# 15-I225-MISC.net
KiCad netlist of a schematic drawn in Altium Designer
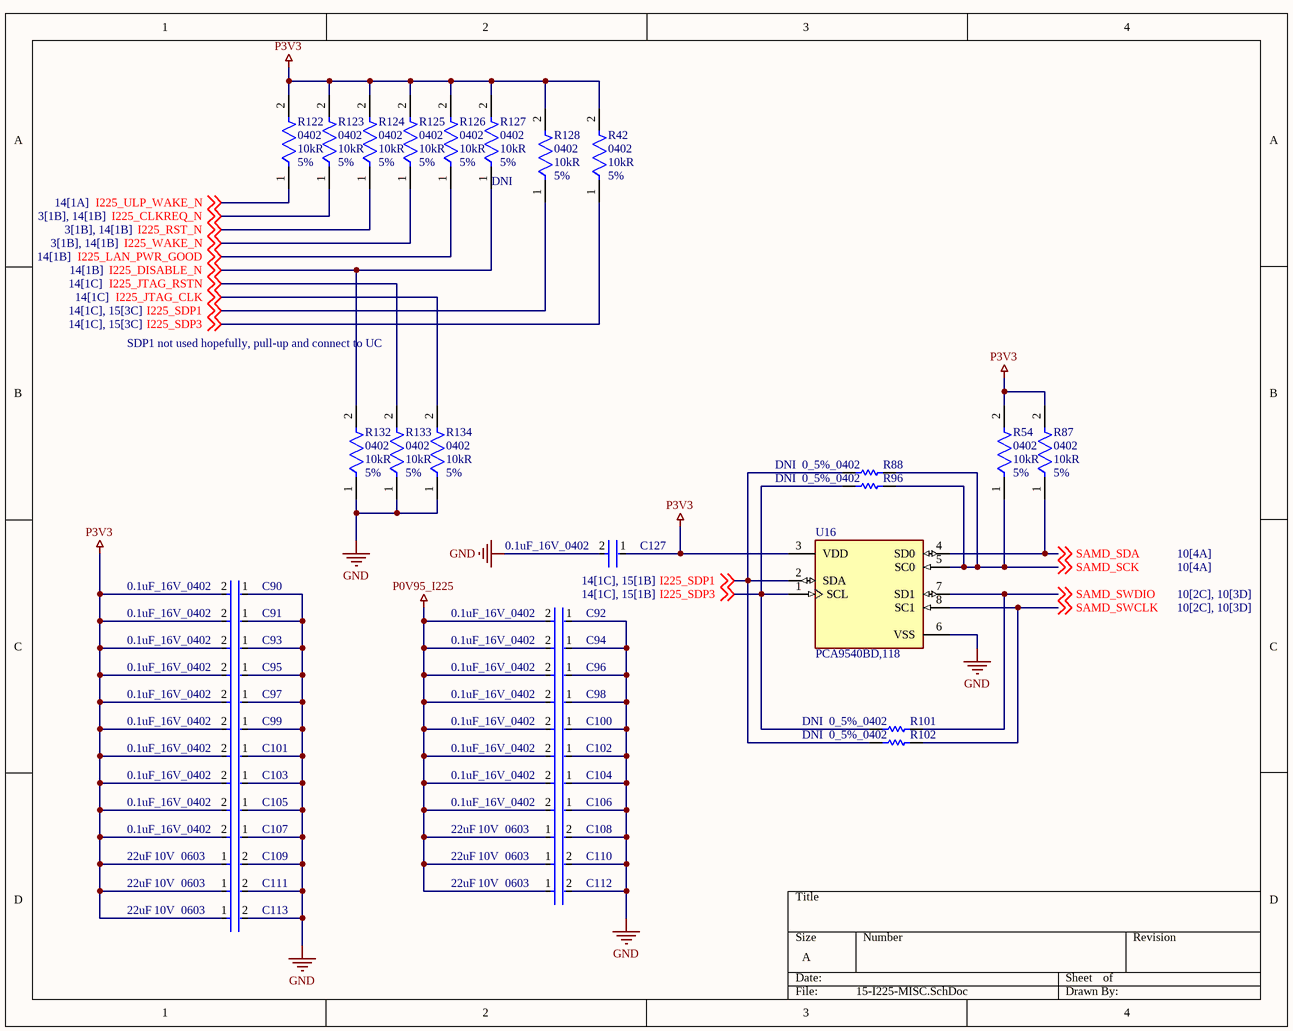
[diagram p0: 15-I225-MISC.SchDoc]

(export (version "E")
  (design (tool "Eeschema 10.0.6"))
  (components
    (comp (ref "C90")
      (value "0.1uF_16V_0402")
      (footprint "FP-GRM15-MFG")
      (description "CAP CER 0.1UF 16V X7R 0402")
      (fields (field (name "MANUFACTURER PART NUMBER") "GRM155R71C104KA88D") (field (name "TOLERANCE") "10%"))
      (libsource (lib "Altium Content Vault") (part "236180d848d6139a670b325ea6854c9"))
    )
    (comp (ref "C91")
      (value "0.1uF_16V_0402")
      (footprint "FP-GRM15-MFG")
      (description "CAP CER 0.1UF 16V X7R 0402")
      (fields (field (name "MANUFACTURER PART NUMBER") "GRM155R71C104KA88D") (field (name "TOLERANCE") "10%"))
      (libsource (lib "Altium Content Vault") (part "236180d848d6139a670b325ea6854c9"))
    )
    (comp (ref "C92")
      (value "0.1uF_16V_0402")
      (footprint "FP-GRM15-MFG")
      (description "CAP CER 0.1UF 16V X7R 0402")
      (fields (field (name "MANUFACTURER PART NUMBER") "GRM155R71C104KA88D") (field (name "TOLERANCE") "10%"))
      (libsource (lib "Altium Content Vault") (part "236180d848d6139a670b325ea6854c9"))
    )
    (comp (ref "C93")
      (value "0.1uF_16V_0402")
      (footprint "FP-GRM15-MFG")
      (description "CAP CER 0.1UF 16V X7R 0402")
      (fields (field (name "MANUFACTURER PART NUMBER") "GRM155R71C104KA88D") (field (name "TOLERANCE") "10%"))
      (libsource (lib "Altium Content Vault") (part "236180d848d6139a670b325ea6854c9"))
    )
    (comp (ref "C94")
      (value "0.1uF_16V_0402")
      (footprint "FP-GRM15-MFG")
      (description "CAP CER 0.1UF 16V X7R 0402")
      (fields (field (name "MANUFACTURER PART NUMBER") "GRM155R71C104KA88D") (field (name "TOLERANCE") "10%"))
      (libsource (lib "Altium Content Vault") (part "236180d848d6139a670b325ea6854c9"))
    )
    (comp (ref "C95")
      (value "0.1uF_16V_0402")
      (footprint "FP-GRM15-MFG")
      (description "CAP CER 0.1UF 16V X7R 0402")
      (fields (field (name "MANUFACTURER PART NUMBER") "GRM155R71C104KA88D") (field (name "TOLERANCE") "10%"))
      (libsource (lib "Altium Content Vault") (part "236180d848d6139a670b325ea6854c9"))
    )
    (comp (ref "C96")
      (value "0.1uF_16V_0402")
      (footprint "FP-GRM15-MFG")
      (description "CAP CER 0.1UF 16V X7R 0402")
      (fields (field (name "MANUFACTURER PART NUMBER") "GRM155R71C104KA88D") (field (name "TOLERANCE") "10%"))
      (libsource (lib "Altium Content Vault") (part "236180d848d6139a670b325ea6854c9"))
    )
    (comp (ref "C97")
      (value "0.1uF_16V_0402")
      (footprint "FP-GRM15-MFG")
      (description "CAP CER 0.1UF 16V X7R 0402")
      (fields (field (name "MANUFACTURER PART NUMBER") "GRM155R71C104KA88D") (field (name "TOLERANCE") "10%"))
      (libsource (lib "Altium Content Vault") (part "236180d848d6139a670b325ea6854c9"))
    )
    (comp (ref "C98")
      (value "0.1uF_16V_0402")
      (footprint "FP-GRM15-MFG")
      (description "CAP CER 0.1UF 16V X7R 0402")
      (fields (field (name "MANUFACTURER PART NUMBER") "GRM155R71C104KA88D") (field (name "TOLERANCE") "10%"))
      (libsource (lib "Altium Content Vault") (part "236180d848d6139a670b325ea6854c9"))
    )
    (comp (ref "C99")
      (value "0.1uF_16V_0402")
      (footprint "FP-GRM15-MFG")
      (description "CAP CER 0.1UF 16V X7R 0402")
      (fields (field (name "MANUFACTURER PART NUMBER") "GRM155R71C104KA88D") (field (name "TOLERANCE") "10%"))
      (libsource (lib "Altium Content Vault") (part "236180d848d6139a670b325ea6854c9"))
    )
    (comp (ref "C100")
      (value "0.1uF_16V_0402")
      (footprint "FP-GRM15-MFG")
      (description "CAP CER 0.1UF 16V X7R 0402")
      (fields (field (name "MANUFACTURER PART NUMBER") "GRM155R71C104KA88D") (field (name "TOLERANCE") "10%"))
      (libsource (lib "Altium Content Vault") (part "236180d848d6139a670b325ea6854c9"))
    )
    (comp (ref "C101")
      (value "0.1uF_16V_0402")
      (footprint "FP-GRM15-MFG")
      (description "CAP CER 0.1UF 16V X7R 0402")
      (fields (field (name "MANUFACTURER PART NUMBER") "GRM155R71C104KA88D") (field (name "TOLERANCE") "10%"))
      (libsource (lib "Altium Content Vault") (part "236180d848d6139a670b325ea6854c9"))
    )
    (comp (ref "C102")
      (value "0.1uF_16V_0402")
      (footprint "FP-GRM15-MFG")
      (description "CAP CER 0.1UF 16V X7R 0402")
      (fields (field (name "MANUFACTURER PART NUMBER") "GRM155R71C104KA88D") (field (name "TOLERANCE") "10%"))
      (libsource (lib "Altium Content Vault") (part "236180d848d6139a670b325ea6854c9"))
    )
    (comp (ref "C103")
      (value "0.1uF_16V_0402")
      (footprint "FP-GRM15-MFG")
      (description "CAP CER 0.1UF 16V X7R 0402")
      (fields (field (name "MANUFACTURER PART NUMBER") "GRM155R71C104KA88D") (field (name "TOLERANCE") "10%"))
      (libsource (lib "Altium Content Vault") (part "236180d848d6139a670b325ea6854c9"))
    )
    (comp (ref "C104")
      (value "0.1uF_16V_0402")
      (footprint "FP-GRM15-MFG")
      (description "CAP CER 0.1UF 16V X7R 0402")
      (fields (field (name "MANUFACTURER PART NUMBER") "GRM155R71C104KA88D") (field (name "TOLERANCE") "10%"))
      (libsource (lib "Altium Content Vault") (part "236180d848d6139a670b325ea6854c9"))
    )
    (comp (ref "C105")
      (value "0.1uF_16V_0402")
      (footprint "FP-GRM15-MFG")
      (description "CAP CER 0.1UF 16V X7R 0402")
      (fields (field (name "MANUFACTURER PART NUMBER") "GRM155R71C104KA88D") (field (name "TOLERANCE") "10%"))
      (libsource (lib "Altium Content Vault") (part "236180d848d6139a670b325ea6854c9"))
    )
    (comp (ref "C106")
      (value "0.1uF_16V_0402")
      (footprint "FP-GRM15-MFG")
      (description "CAP CER 0.1UF 16V X7R 0402")
      (fields (field (name "MANUFACTURER PART NUMBER") "GRM155R71C104KA88D") (field (name "TOLERANCE") "10%"))
      (libsource (lib "Altium Content Vault") (part "236180d848d6139a670b325ea6854c9"))
    )
    (comp (ref "C107")
      (value "0.1uF_16V_0402")
      (footprint "FP-GRM15-MFG")
      (description "CAP CER 0.1UF 16V X7R 0402")
      (fields (field (name "MANUFACTURER PART NUMBER") "GRM155R71C104KA88D") (field (name "TOLERANCE") "10%"))
      (libsource (lib "Altium Content Vault") (part "236180d848d6139a670b325ea6854c9"))
    )
    (comp (ref "C108")
      (value "GRM188R61A226ME15D")
      (footprint "FP-GRM188-0_2-IPC_C")
      (description "Chip Multilayer Ceramic Capacitors for General Purpose, 0603, 22uF, X5R, 15%, 20%, 10V")
      (fields
        (field (name "TOLERANCE") "20%")
        (field (name "CAPACITANCE") "22uF")
        (field (name "VOLTAGE RATING") "10V")
        (field (name "CASE CODE (IMPERIAL)") "0603")
      )
      (libsource (lib "Altium Content Vault") (part "11868f565c42a9108669ba33697ecf6"))
    )
    (comp (ref "C109")
      (value "GRM188R61A226ME15D")
      (footprint "FP-GRM188-0_2-IPC_C")
      (description "Chip Multilayer Ceramic Capacitors for General Purpose, 0603, 22uF, X5R, 15%, 20%, 10V")
      (fields
        (field (name "TOLERANCE") "20%")
        (field (name "CAPACITANCE") "22uF")
        (field (name "VOLTAGE RATING") "10V")
        (field (name "CASE CODE (IMPERIAL)") "0603")
      )
      (libsource (lib "Altium Content Vault") (part "11868f565c42a9108669ba33697ecf6"))
    )
    (comp (ref "C110")
      (value "GRM188R61A226ME15D")
      (footprint "FP-GRM188-0_2-IPC_C")
      (description "Chip Multilayer Ceramic Capacitors for General Purpose, 0603, 22uF, X5R, 15%, 20%, 10V")
      (fields
        (field (name "TOLERANCE") "20%")
        (field (name "CAPACITANCE") "22uF")
        (field (name "VOLTAGE RATING") "10V")
        (field (name "CASE CODE (IMPERIAL)") "0603")
      )
      (libsource (lib "Altium Content Vault") (part "11868f565c42a9108669ba33697ecf6"))
    )
    (comp (ref "C111")
      (value "GRM188R61A226ME15D")
      (footprint "FP-GRM188-0_2-IPC_C")
      (description "Chip Multilayer Ceramic Capacitors for General Purpose, 0603, 22uF, X5R, 15%, 20%, 10V")
      (fields
        (field (name "TOLERANCE") "20%")
        (field (name "CAPACITANCE") "22uF")
        (field (name "VOLTAGE RATING") "10V")
        (field (name "CASE CODE (IMPERIAL)") "0603")
      )
      (libsource (lib "Altium Content Vault") (part "11868f565c42a9108669ba33697ecf6"))
    )
    (comp (ref "C112")
      (value "GRM188R61A226ME15D")
      (footprint "FP-GRM188-0_2-IPC_C")
      (description "Chip Multilayer Ceramic Capacitors for General Purpose, 0603, 22uF, X5R, 15%, 20%, 10V")
      (fields
        (field (name "TOLERANCE") "20%")
        (field (name "CAPACITANCE") "22uF")
        (field (name "VOLTAGE RATING") "10V")
        (field (name "CASE CODE (IMPERIAL)") "0603")
      )
      (libsource (lib "Altium Content Vault") (part "11868f565c42a9108669ba33697ecf6"))
    )
    (comp (ref "C113")
      (value "GRM188R61A226ME15D")
      (footprint "FP-GRM188-0_2-IPC_C")
      (description "Chip Multilayer Ceramic Capacitors for General Purpose, 0603, 22uF, X5R, 15%, 20%, 10V")
      (fields
        (field (name "TOLERANCE") "20%")
        (field (name "CAPACITANCE") "22uF")
        (field (name "VOLTAGE RATING") "10V")
        (field (name "CASE CODE (IMPERIAL)") "0603")
      )
      (libsource (lib "Altium Content Vault") (part "11868f565c42a9108669ba33697ecf6"))
    )
    (comp (ref "C127")
      (value "0.1uF_16V_0402")
      (footprint "FP-GRM15-MFG")
      (description "CAP CER 0.1UF 16V X7R 0402")
      (fields (field (name "MANUFACTURER PART NUMBER") "GRM155R71C104KA88D") (field (name "TOLERANCE") "10%"))
      (libsource (lib "Altium Content Vault") (part "236180d848d6139a670b325ea6854c9"))
    )
    (comp (ref "R42")
      (value "CRCW040210K0JNED")
      (footprint "FP-CRCW0402-e3-IPC_B")
      (description "RES Thick Film, 10kΩ, 5%, 0.063W, 200ppm/°C, 0402")
      (fields
        (field (name "CASE/PACKAGE") "0402")
        (field (name "RESISTANCE") "10kR")
        (field (name "TOLERANCE") "5%")
      )
      (libsource (lib "Altium Content Vault") (part "1029c3af85768c4190bb7ad29bc67b5"))
    )
    (comp (ref "R54")
      (value "CRCW040210K0JNED")
      (footprint "FP-CRCW0402-e3-IPC_B")
      (description "RES Thick Film, 10kΩ, 5%, 0.063W, 200ppm/°C, 0402")
      (fields
        (field (name "CASE/PACKAGE") "0402")
        (field (name "RESISTANCE") "10kR")
        (field (name "TOLERANCE") "5%")
      )
      (libsource (lib "Altium Content Vault") (part "1029c3af85768c4190bb7ad29bc67b5"))
    )
    (comp (ref "R87")
      (value "CRCW040210K0JNED")
      (footprint "FP-CRCW0402-e3-IPC_B")
      (description "RES Thick Film, 10kΩ, 5%, 0.063W, 200ppm/°C, 0402")
      (fields
        (field (name "CASE/PACKAGE") "0402")
        (field (name "RESISTANCE") "10kR")
        (field (name "TOLERANCE") "5%")
      )
      (libsource (lib "Altium Content Vault") (part "1029c3af85768c4190bb7ad29bc67b5"))
    )
    (comp (ref "R88")
      (value "0_5%_0402")
      (footprint "RESC1005X40X25LL10T10")
      (fields
        (field (name "MANUFACTURER") "KOA Speer")
        (field (name "PART NUMBER") "RK73Z1ETTP")
        (field (name "DNI") "DNI")
      )
      (libsource (lib "Altium Content Vault") (part "RES"))
    )
    (comp (ref "R96")
      (value "0_5%_0402")
      (footprint "RESC1005X40X25LL10T10")
      (fields
        (field (name "MANUFACTURER") "KOA Speer")
        (field (name "PART NUMBER") "RK73Z1ETTP")
        (field (name "DNI") "DNI")
      )
      (libsource (lib "Altium Content Vault") (part "RES"))
    )
    (comp (ref "R101")
      (value "0_5%_0402")
      (footprint "RESC1005X40X25LL10T10")
      (fields
        (field (name "MANUFACTURER") "KOA Speer")
        (field (name "PART NUMBER") "RK73Z1ETTP")
        (field (name "DNI") "DNI")
      )
      (libsource (lib "Altium Content Vault") (part "RES"))
    )
    (comp (ref "R102")
      (value "0_5%_0402")
      (footprint "RESC1005X40X25LL10T10")
      (fields
        (field (name "MANUFACTURER") "KOA Speer")
        (field (name "PART NUMBER") "RK73Z1ETTP")
        (field (name "DNI") "DNI")
      )
      (libsource (lib "Altium Content Vault") (part "RES"))
    )
    (comp (ref "R122")
      (value "CRCW040210K0JNED")
      (footprint "FP-CRCW0402-e3-IPC_B")
      (description "RES Thick Film, 10kΩ, 5%, 0.063W, 200ppm/°C, 0402")
      (fields
        (field (name "CASE/PACKAGE") "0402")
        (field (name "RESISTANCE") "10kR")
        (field (name "TOLERANCE") "5%")
      )
      (libsource (lib "Altium Content Vault") (part "1029c3af85768c4190bb7ad29bc67b5"))
    )
    (comp (ref "R123")
      (value "CRCW040210K0JNED")
      (footprint "FP-CRCW0402-e3-IPC_B")
      (description "RES Thick Film, 10kΩ, 5%, 0.063W, 200ppm/°C, 0402")
      (fields
        (field (name "CASE/PACKAGE") "0402")
        (field (name "RESISTANCE") "10kR")
        (field (name "TOLERANCE") "5%")
      )
      (libsource (lib "Altium Content Vault") (part "1029c3af85768c4190bb7ad29bc67b5"))
    )
    (comp (ref "R124")
      (value "CRCW040210K0JNED")
      (footprint "FP-CRCW0402-e3-IPC_B")
      (description "RES Thick Film, 10kΩ, 5%, 0.063W, 200ppm/°C, 0402")
      (fields
        (field (name "CASE/PACKAGE") "0402")
        (field (name "RESISTANCE") "10kR")
        (field (name "TOLERANCE") "5%")
      )
      (libsource (lib "Altium Content Vault") (part "1029c3af85768c4190bb7ad29bc67b5"))
    )
    (comp (ref "R125")
      (value "CRCW040210K0JNED")
      (footprint "FP-CRCW0402-e3-IPC_B")
      (description "RES Thick Film, 10kΩ, 5%, 0.063W, 200ppm/°C, 0402")
      (fields
        (field (name "CASE/PACKAGE") "0402")
        (field (name "RESISTANCE") "10kR")
        (field (name "TOLERANCE") "5%")
      )
      (libsource (lib "Altium Content Vault") (part "1029c3af85768c4190bb7ad29bc67b5"))
    )
    (comp (ref "R126")
      (value "CRCW040210K0JNED")
      (footprint "FP-CRCW0402-e3-IPC_B")
      (description "RES Thick Film, 10kΩ, 5%, 0.063W, 200ppm/°C, 0402")
      (fields
        (field (name "CASE/PACKAGE") "0402")
        (field (name "RESISTANCE") "10kR")
        (field (name "TOLERANCE") "5%")
      )
      (libsource (lib "Altium Content Vault") (part "1029c3af85768c4190bb7ad29bc67b5"))
    )
    (comp (ref "R127")
      (value "CRCW040210K0JNED")
      (footprint "FP-CRCW0402-e3-IPC_B")
      (description "RES Thick Film, 10kΩ, 5%, 0.063W, 200ppm/°C, 0402")
      (fields
        (field (name "CASE/PACKAGE") "0402")
        (field (name "RESISTANCE") "10kR")
        (field (name "TOLERANCE") "5%")
        (field (name "DNI") "DNI")
      )
      (libsource (lib "Altium Content Vault") (part "1029c3af85768c4190bb7ad29bc67b5"))
    )
    (comp (ref "R128")
      (value "CRCW040210K0JNED")
      (footprint "FP-CRCW0402-e3-IPC_B")
      (description "RES Thick Film, 10kΩ, 5%, 0.063W, 200ppm/°C, 0402")
      (fields
        (field (name "CASE/PACKAGE") "0402")
        (field (name "RESISTANCE") "10kR")
        (field (name "TOLERANCE") "5%")
      )
      (libsource (lib "Altium Content Vault") (part "1029c3af85768c4190bb7ad29bc67b5"))
    )
    (comp (ref "R132")
      (value "CRCW040210K0JNED")
      (footprint "FP-CRCW0402-e3-IPC_B")
      (description "RES Thick Film, 10kΩ, 5%, 0.063W, 200ppm/°C, 0402")
      (fields
        (field (name "CASE/PACKAGE") "0402")
        (field (name "RESISTANCE") "10kR")
        (field (name "TOLERANCE") "5%")
      )
      (libsource (lib "Altium Content Vault") (part "1029c3af85768c4190bb7ad29bc67b5"))
    )
    (comp (ref "R133")
      (value "CRCW040210K0JNED")
      (footprint "FP-CRCW0402-e3-IPC_B")
      (description "RES Thick Film, 10kΩ, 5%, 0.063W, 200ppm/°C, 0402")
      (fields
        (field (name "CASE/PACKAGE") "0402")
        (field (name "RESISTANCE") "10kR")
        (field (name "TOLERANCE") "5%")
      )
      (libsource (lib "Altium Content Vault") (part "1029c3af85768c4190bb7ad29bc67b5"))
    )
    (comp (ref "R134")
      (value "CRCW040210K0JNED")
      (footprint "FP-CRCW0402-e3-IPC_B")
      (description "RES Thick Film, 10kΩ, 5%, 0.063W, 200ppm/°C, 0402")
      (fields
        (field (name "CASE/PACKAGE") "0402")
        (field (name "RESISTANCE") "10kR")
        (field (name "TOLERANCE") "5%")
      )
      (libsource (lib "Altium Content Vault") (part "1029c3af85768c4190bb7ad29bc67b5"))
    )
    (comp (ref "U16")
      (value "PCA9540BD,118")
      (footprint "FP-SOT96-1-MFG")
      (description "IC INTERFACE SPECIALIZED 8SO")
      (libsource (lib "Altium Content Vault") (part "5c17f1dafb921066753f6c1bed119c2"))
    )
  )
  (nets
    (net (code "1") (name "GND") (class "Default")
      (node (ref "C100") (pin "1") (pinfunction "1_1") (pintype "passive"))
      (node (ref "C101") (pin "1") (pinfunction "1_1") (pintype "passive"))
      (node (ref "C102") (pin "1") (pinfunction "1_1") (pintype "passive"))
      (node (ref "C103") (pin "1") (pinfunction "1_1") (pintype "passive"))
      (node (ref "C104") (pin "1") (pinfunction "1_1") (pintype "passive"))
      (node (ref "C105") (pin "1") (pinfunction "1_1") (pintype "passive"))
      (node (ref "C106") (pin "1") (pinfunction "1_1") (pintype "passive"))
      (node (ref "C107") (pin "1") (pinfunction "1_1") (pintype "passive"))
      (node (ref "C108") (pin "2") (pinfunction "2_2") (pintype "passive"))
      (node (ref "C109") (pin "2") (pinfunction "2_2") (pintype "passive"))
      (node (ref "C110") (pin "2") (pinfunction "2_2") (pintype "passive"))
      (node (ref "C111") (pin "2") (pinfunction "2_2") (pintype "passive"))
      (node (ref "C112") (pin "2") (pinfunction "2_2") (pintype "passive"))
      (node (ref "C113") (pin "2") (pinfunction "2_2") (pintype "passive"))
      (node (ref "C127") (pin "2") (pinfunction "2_2") (pintype "passive"))
      (node (ref "C90") (pin "1") (pinfunction "1_1") (pintype "passive"))
      (node (ref "C91") (pin "1") (pinfunction "1_1") (pintype "passive"))
      (node (ref "C92") (pin "1") (pinfunction "1_1") (pintype "passive"))
      (node (ref "C93") (pin "1") (pinfunction "1_1") (pintype "passive"))
      (node (ref "C94") (pin "1") (pinfunction "1_1") (pintype "passive"))
      (node (ref "C95") (pin "1") (pinfunction "1_1") (pintype "passive"))
      (node (ref "C96") (pin "1") (pinfunction "1_1") (pintype "passive"))
      (node (ref "C97") (pin "1") (pinfunction "1_1") (pintype "passive"))
      (node (ref "C98") (pin "1") (pinfunction "1_1") (pintype "passive"))
      (node (ref "C99") (pin "1") (pinfunction "1_1") (pintype "passive"))
      (node (ref "R132") (pin "1") (pinfunction "1_1") (pintype "passive"))
      (node (ref "R133") (pin "1") (pinfunction "1_1") (pintype "passive"))
      (node (ref "R134") (pin "1") (pinfunction "1_1") (pintype "passive"))
      (node (ref "U16") (pin "6") (pinfunction "VSS_6") (pintype "power_in"))
    )
    (net (code "2") (name "I225_CLKREQ_N") (class "Default")
      (node (ref "R123") (pin "1") (pinfunction "1_1") (pintype "passive"))
    )
    (net (code "3") (name "I225_DISABLE_N") (class "Default")
      (node (ref "R127") (pin "1") (pinfunction "1_1") (pintype "passive"))
      (node (ref "R132") (pin "2") (pinfunction "2_2") (pintype "passive"))
    )
    (net (code "4") (name "I225_JTAG_CLK") (class "Default")
      (node (ref "R134") (pin "2") (pinfunction "2_2") (pintype "passive"))
    )
    (net (code "5") (name "I225_JTAG_RSTN") (class "Default")
      (node (ref "R133") (pin "2") (pinfunction "2_2") (pintype "passive"))
    )
    (net (code "6") (name "I225_LAN_PWR_GOOD") (class "Default")
      (node (ref "R126") (pin "1") (pinfunction "1_1") (pintype "passive"))
    )
    (net (code "7") (name "I225_RST_N") (class "Default")
      (node (ref "R124") (pin "1") (pinfunction "1_1") (pintype "passive"))
    )
    (net (code "8") (name "I225_SDP1") (class "Default")
      (node (ref "R102") (pin "1") (pinfunction "1_1") (pintype "passive"))
      (node (ref "R128") (pin "1") (pinfunction "1_1") (pintype "passive"))
      (node (ref "R88") (pin "1") (pinfunction "1_1") (pintype "passive"))
      (node (ref "U16") (pin "2") (pinfunction "SDA_2") (pintype "bidirectional"))
    )
    (net (code "9") (name "I225_SDP3") (class "Default")
      (node (ref "R101") (pin "1") (pinfunction "1_1") (pintype "passive"))
      (node (ref "R42") (pin "1") (pinfunction "1_1") (pintype "passive"))
      (node (ref "R96") (pin "1") (pinfunction "1_1") (pintype "passive"))
      (node (ref "U16") (pin "1") (pinfunction "SCL_1") (pintype "input"))
    )
    (net (code "10") (name "I225_ULP_WAKE_N") (class "Default")
      (node (ref "R122") (pin "1") (pinfunction "1_1") (pintype "passive"))
    )
    (net (code "11") (name "I225_WAKE_N") (class "Default")
      (node (ref "R125") (pin "1") (pinfunction "1_1") (pintype "passive"))
    )
    (net (code "12") (name "P0V95_I225") (class "Default")
      (node (ref "C100") (pin "2") (pinfunction "2_2") (pintype "passive"))
      (node (ref "C102") (pin "2") (pinfunction "2_2") (pintype "passive"))
      (node (ref "C104") (pin "2") (pinfunction "2_2") (pintype "passive"))
      (node (ref "C106") (pin "2") (pinfunction "2_2") (pintype "passive"))
      (node (ref "C108") (pin "1") (pinfunction "1_1") (pintype "passive"))
      (node (ref "C110") (pin "1") (pinfunction "1_1") (pintype "passive"))
      (node (ref "C112") (pin "1") (pinfunction "1_1") (pintype "passive"))
      (node (ref "C92") (pin "2") (pinfunction "2_2") (pintype "passive"))
      (node (ref "C94") (pin "2") (pinfunction "2_2") (pintype "passive"))
      (node (ref "C96") (pin "2") (pinfunction "2_2") (pintype "passive"))
      (node (ref "C98") (pin "2") (pinfunction "2_2") (pintype "passive"))
    )
    (net (code "13") (name "P3V3") (class "Default")
      (node (ref "C101") (pin "2") (pinfunction "2_2") (pintype "passive"))
      (node (ref "C103") (pin "2") (pinfunction "2_2") (pintype "passive"))
      (node (ref "C105") (pin "2") (pinfunction "2_2") (pintype "passive"))
      (node (ref "C107") (pin "2") (pinfunction "2_2") (pintype "passive"))
      (node (ref "C109") (pin "1") (pinfunction "1_1") (pintype "passive"))
      (node (ref "C111") (pin "1") (pinfunction "1_1") (pintype "passive"))
      (node (ref "C113") (pin "1") (pinfunction "1_1") (pintype "passive"))
      (node (ref "C127") (pin "1") (pinfunction "1_1") (pintype "passive"))
      (node (ref "C90") (pin "2") (pinfunction "2_2") (pintype "passive"))
      (node (ref "C91") (pin "2") (pinfunction "2_2") (pintype "passive"))
      (node (ref "C93") (pin "2") (pinfunction "2_2") (pintype "passive"))
      (node (ref "C95") (pin "2") (pinfunction "2_2") (pintype "passive"))
      (node (ref "C97") (pin "2") (pinfunction "2_2") (pintype "passive"))
      (node (ref "C99") (pin "2") (pinfunction "2_2") (pintype "passive"))
      (node (ref "R122") (pin "2") (pinfunction "2_2") (pintype "passive"))
      (node (ref "R123") (pin "2") (pinfunction "2_2") (pintype "passive"))
      (node (ref "R124") (pin "2") (pinfunction "2_2") (pintype "passive"))
      (node (ref "R125") (pin "2") (pinfunction "2_2") (pintype "passive"))
      (node (ref "R126") (pin "2") (pinfunction "2_2") (pintype "passive"))
      (node (ref "R127") (pin "2") (pinfunction "2_2") (pintype "passive"))
      (node (ref "R128") (pin "2") (pinfunction "2_2") (pintype "passive"))
      (node (ref "R42") (pin "2") (pinfunction "2_2") (pintype "passive"))
      (node (ref "R54") (pin "2") (pinfunction "2_2") (pintype "passive"))
      (node (ref "R87") (pin "2") (pinfunction "2_2") (pintype "passive"))
      (node (ref "U16") (pin "3") (pinfunction "VDD_3") (pintype "power_in"))
    )
    (net (code "14") (name "SAMD_SCK") (class "Default")
      (node (ref "R54") (pin "1") (pinfunction "1_1") (pintype "passive"))
      (node (ref "R88") (pin "2") (pinfunction "2_2") (pintype "passive"))
      (node (ref "R96") (pin "2") (pinfunction "2_2") (pintype "passive"))
      (node (ref "U16") (pin "5") (pinfunction "SC0_5") (pintype "input"))
    )
    (net (code "15") (name "SAMD_SDA") (class "Default")
      (node (ref "R87") (pin "1") (pinfunction "1_1") (pintype "passive"))
      (node (ref "U16") (pin "4") (pinfunction "SD0_4") (pintype "bidirectional"))
    )
    (net (code "16") (name "SAMD_SWCLK") (class "Default")
      (node (ref "R102") (pin "2") (pinfunction "2_2") (pintype "passive"))
      (node (ref "U16") (pin "8") (pinfunction "SC1_8") (pintype "input"))
    )
    (net (code "17") (name "SAMD_SWDIO") (class "Default")
      (node (ref "R101") (pin "2") (pinfunction "2_2") (pintype "passive"))
      (node (ref "U16") (pin "7") (pinfunction "SD1_7") (pintype "bidirectional"))
    )
  )
)
